# SML_IR-Sensor.net
KiCad netlist of a schematic drawn in EAGLE
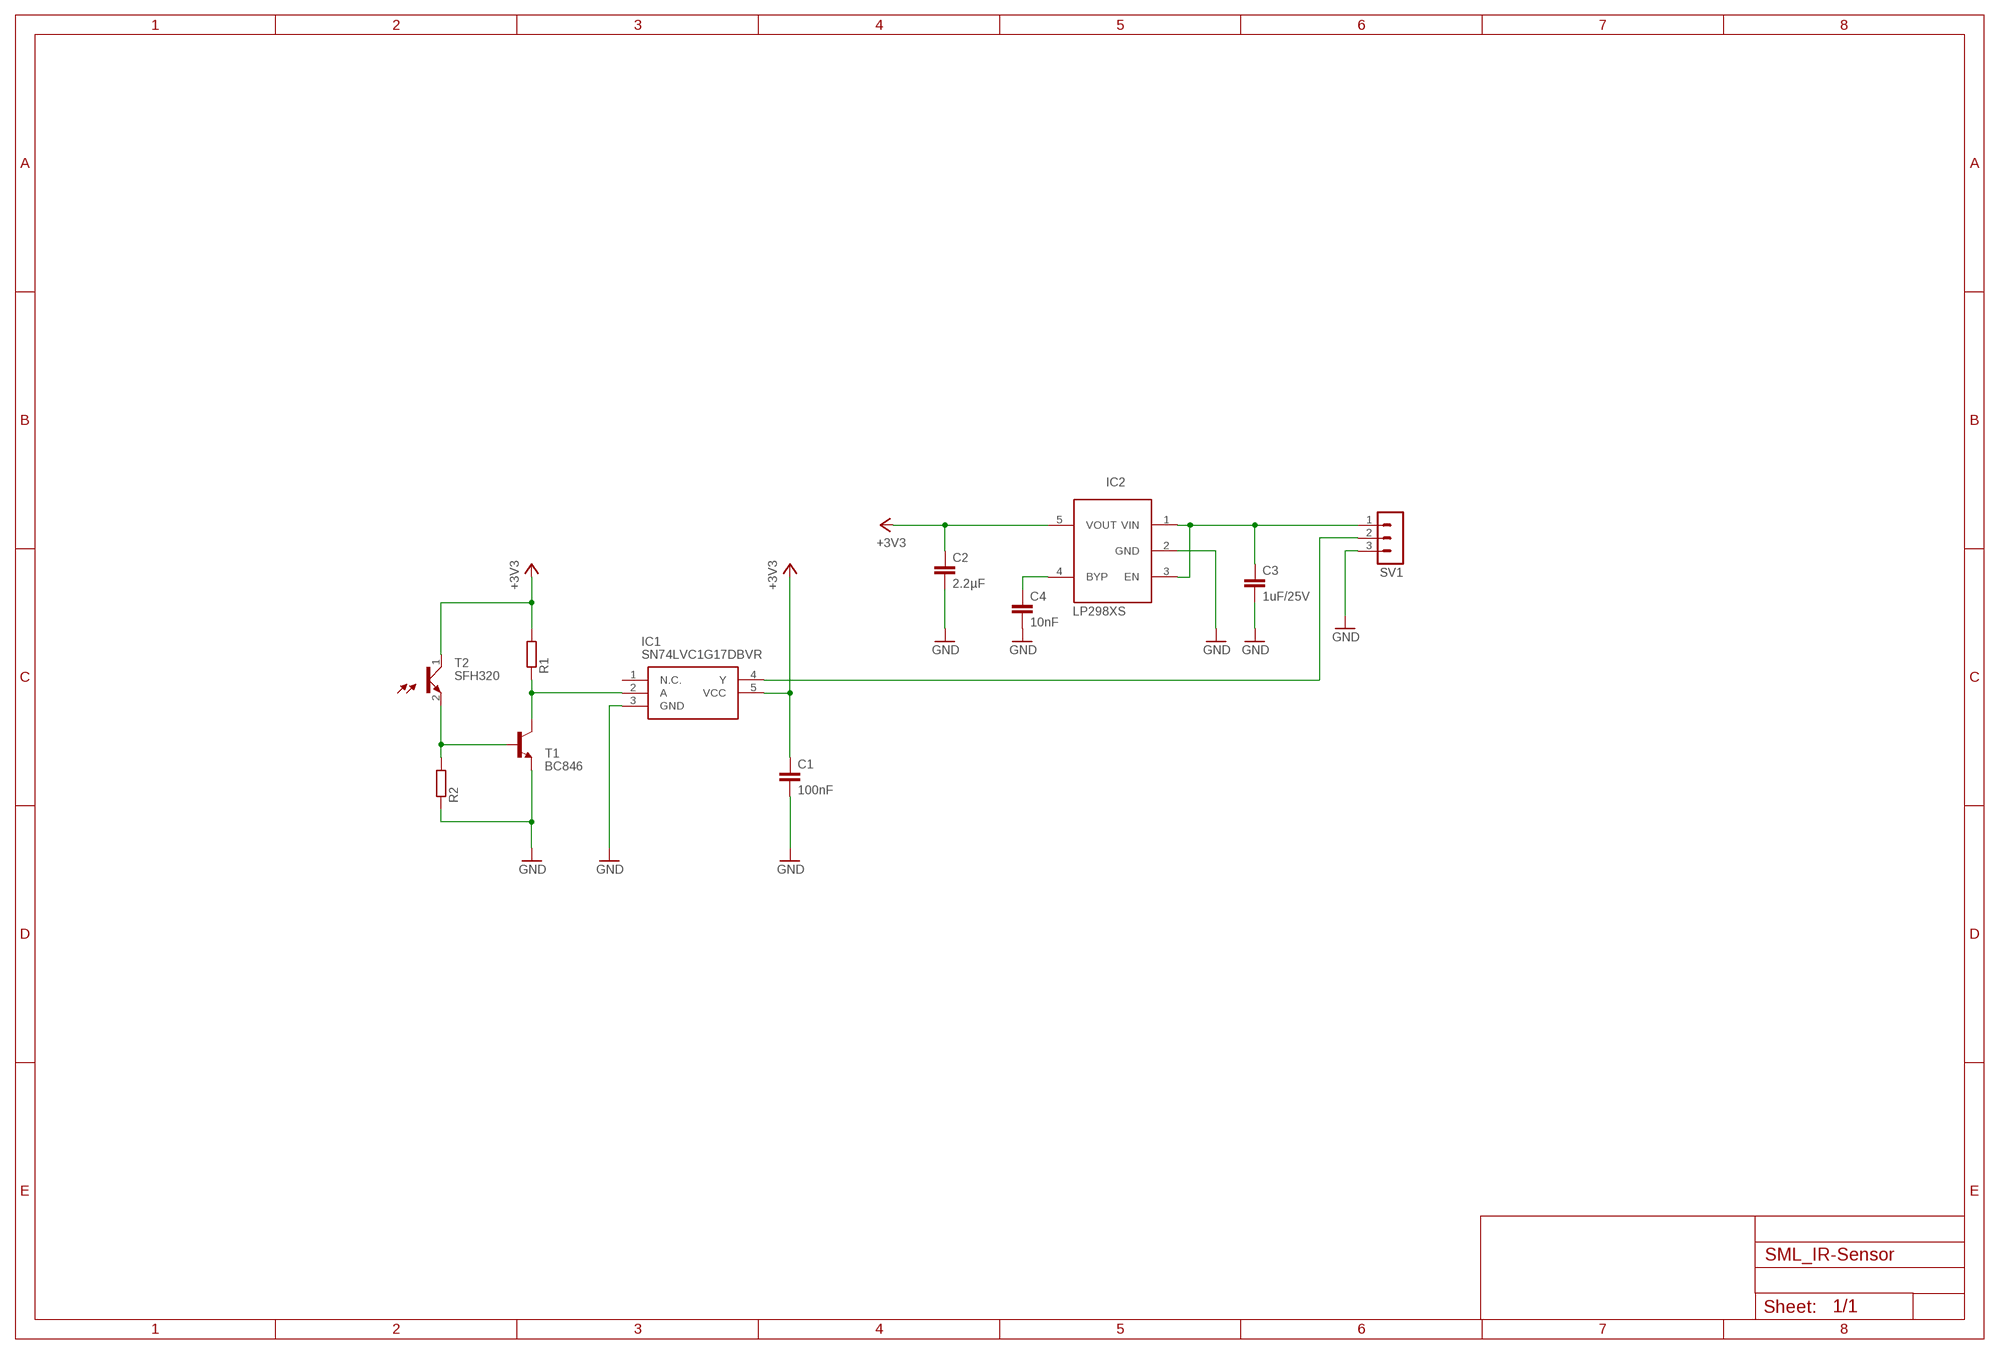
[diagram p0: schematic, sheet 1]

(export (version "E")
  (design (tool "Eeschema 10.0.6"))
  (components
    (comp (ref "C1")
      (value "100nF")
      (footprint "eagle-import:C0603")
      (libsource (lib "eagle-import") (part "C-EUC0603"))
    )
    (comp (ref "C2")
      (value "2.2µF")
      (footprint "eagle-import:C0603")
      (libsource (lib "eagle-import") (part "C-EUC0603"))
    )
    (comp (ref "C3")
      (value "1uF/25V")
      (footprint "eagle-import:C0603")
      (libsource (lib "eagle-import") (part "C-EUC0603"))
    )
    (comp (ref "C4")
      (value "10nF")
      (footprint "eagle-import:C0603")
      (libsource (lib "eagle-import") (part "C-EUC0603"))
    )
    (comp (ref "IC1")
      (value "SN74LVC1G17DBVR")
      (footprint "eagle-import:SOT95P280X145-5N")
      (fields (field (name "MOUSER_PART_NUMBER") "595-SN74LVC1G17DBVR"))
      (libsource (lib "eagle-import") (part "SN74LVC1G17DBVR"))
    )
    (comp (ref "IC2")
      (value "LP298XS")
      (footprint "eagle-import:SOT23-5L")
      (libsource (lib "eagle-import") (part "LP298XS"))
    )
    (comp (ref "R1")
      (value "R-EU_R0603")
      (footprint "eagle-import:R0603")
      (libsource (lib "eagle-import") (part "R-EU_R0603"))
    )
    (comp (ref "R2")
      (value "R-EU_R0603")
      (footprint "eagle-import:R0603")
      (libsource (lib "eagle-import") (part "R-EU_R0603"))
    )
    (comp (ref "SV1")
      (value "MA03-1")
      (footprint "eagle-import:MA03-1")
      (libsource (lib "eagle-import") (part "MA03-1"))
    )
    (comp (ref "T1")
      (value "BC846")
      (footprint "eagle-import:SOT23")
      (libsource (lib "eagle-import") (part "BC846"))
    )
    (comp (ref "T2")
      (value "SFH320")
      (footprint "eagle-import:LEDM3528X210N")
      (fields (field (name "MOUSER_PART_NUMBER") "720-SFH320D2471"))
      (libsource (lib "eagle-import") (part "SFH320"))
    )
  )
  (nets
    (net (code "1") (name "+3V3") (class "Default")
      (node (ref "C1") (pin "1") (pinfunction "1_1") (pintype "passive"))
      (node (ref "C2") (pin "1") (pinfunction "1_1") (pintype "passive"))
      (node (ref "IC1") (pin "5") (pinfunction "VCC_5") (pintype "bidirectional"))
      (node (ref "IC2") (pin "5") (pinfunction "VOUT_5") (pintype "bidirectional"))
      (node (ref "R1") (pin "2") (pinfunction "2_2") (pintype "passive"))
      (node (ref "T2") (pin "1") (pinfunction "C_1") (pintype "bidirectional"))
    )
    (net (code "2") (name "GND") (class "Default")
      (node (ref "C1") (pin "2") (pinfunction "2_2") (pintype "passive"))
      (node (ref "C2") (pin "2") (pinfunction "2_2") (pintype "passive"))
      (node (ref "C3") (pin "2") (pinfunction "2_2") (pintype "passive"))
      (node (ref "C4") (pin "2") (pinfunction "2_2") (pintype "passive"))
      (node (ref "IC1") (pin "3") (pinfunction "GND_3") (pintype "bidirectional"))
      (node (ref "IC2") (pin "2") (pinfunction "GND_2") (pintype "bidirectional"))
      (node (ref "R2") (pin "1") (pinfunction "1_1") (pintype "passive"))
      (node (ref "SV1") (pin "3") (pinfunction "3_3") (pintype "passive"))
      (node (ref "T1") (pin "2") (pinfunction "E_2") (pintype "passive"))
    )
    (net (code "3") (name "Net-(IC1-A)") (class "Default")
      (node (ref "IC1") (pin "2") (pinfunction "A_2") (pintype "bidirectional"))
      (node (ref "R1") (pin "1") (pinfunction "1_1") (pintype "passive"))
      (node (ref "T1") (pin "3") (pinfunction "C_3") (pintype "passive"))
    )
    (net (code "4") (name "Net-(IC1-Y)") (class "Default")
      (node (ref "IC1") (pin "4") (pinfunction "Y_4") (pintype "bidirectional"))
      (node (ref "SV1") (pin "2") (pinfunction "2_2") (pintype "passive"))
    )
    (net (code "5") (name "Net-(IC2-BYP)") (class "Default")
      (node (ref "C4") (pin "1") (pinfunction "1_1") (pintype "passive"))
      (node (ref "IC2") (pin "4") (pinfunction "BYP_4") (pintype "bidirectional"))
    )
    (net (code "6") (name "Net-(IC2-EN)") (class "Default")
      (node (ref "C3") (pin "1") (pinfunction "1_1") (pintype "passive"))
      (node (ref "IC2") (pin "1") (pinfunction "VIN_1") (pintype "bidirectional"))
      (node (ref "IC2") (pin "3") (pinfunction "EN_3") (pintype "bidirectional"))
      (node (ref "SV1") (pin "1") (pinfunction "1_1") (pintype "passive"))
    )
    (net (code "7") (name "Net-(T1-B)") (class "Default")
      (node (ref "R2") (pin "2") (pinfunction "2_2") (pintype "passive"))
      (node (ref "T1") (pin "1") (pinfunction "B_1") (pintype "passive"))
      (node (ref "T2") (pin "2") (pinfunction "E_2") (pintype "bidirectional"))
    )
    (net (code "8") (name "unconnected-(IC1-N.C.-Pad1)") (class "Default")
      (node (ref "IC1") (pin "1") (pinfunction "N.C._1") (pintype "no_connect"))
    )
  )
)
